# WiFi.net
KiCad netlist of a schematic drawn in Altium Designer
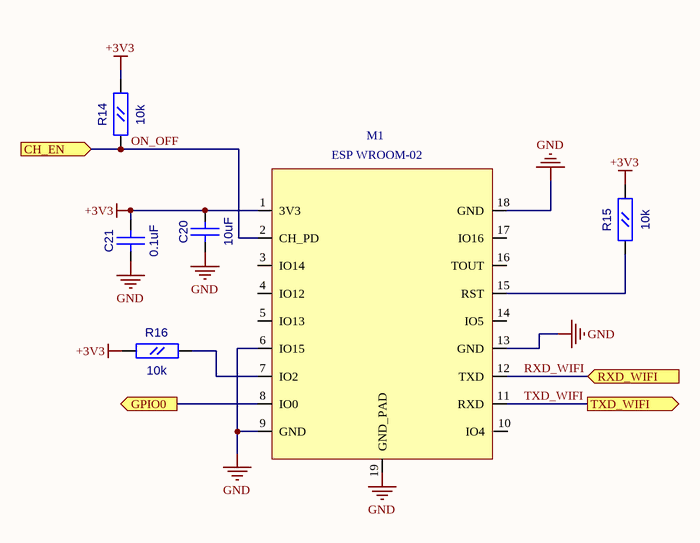
[diagram p0: WiFi.SchDoc]

(export (version "E")
  (design (tool "Eeschema 10.0.6"))
  (components
    (comp (ref "C20")
      (value "10uF")
      (footprint "CC0805")
      (description "CC0805")
      (libsource (lib "gprs_modem_2") (part "CC0805"))
    )
    (comp (ref "C21")
      (value "0.1uF")
      (footprint "CC0603")
      (description "CC0603")
      (libsource (lib "gprs_modem_2") (part "CC0603"))
    )
    (comp (ref "M1")
      (value "ESP WROOM-02")
      (footprint "ESP-WOORM-02")
      (libsource (lib "gprs_modem_2") (part "ESP-WROOM-02"))
    )
    (comp (ref "R14")
      (value "10k")
      (footprint "RC0603")
      (description "RC0603")
      (libsource (lib "gprs_modem_2") (part "RC0603"))
    )
    (comp (ref "R15")
      (value "10k")
      (footprint "RC0603")
      (description "RC0603")
      (libsource (lib "gprs_modem_2") (part "RC0603"))
    )
    (comp (ref "R16")
      (value "10k")
      (footprint "RC0603")
      (description "RC0603")
      (libsource (lib "gprs_modem_2") (part "RC0603"))
    )
  )
  (nets
    (net (code "1") (name "+3V3") (class "Default")
      (node (ref "C20") (pin "2") (pinfunction "B_2") (pintype "passive"))
      (node (ref "C21") (pin "2") (pinfunction "B_2") (pintype "passive"))
      (node (ref "M1") (pin "1") (pinfunction "3V3_1") (pintype "passive"))
      (node (ref "R14") (pin "2") (pinfunction "B_2") (pintype "passive"))
      (node (ref "R15") (pin "2") (pinfunction "B_2") (pintype "passive"))
      (node (ref "R16") (pin "1") (pinfunction "A_1") (pintype "passive"))
    )
    (net (code "2") (name "/GPIO0") (class "Default")
      (node (ref "M1") (pin "8") (pinfunction "IO0_8") (pintype "passive"))
    )
    (net (code "3") (name "/ON_OFF") (class "Default")
      (node (ref "M1") (pin "2") (pinfunction "CH_PD_2") (pintype "passive"))
      (node (ref "R14") (pin "1") (pinfunction "A_1") (pintype "passive"))
    )
    (net (code "4") (name "/RXD_WIFI") (class "Default")
      (node (ref "M1") (pin "12") (pinfunction "TXD_12") (pintype "passive"))
    )
    (net (code "5") (name "/TXD_WIFI") (class "Default")
      (node (ref "M1") (pin "11") (pinfunction "RXD_11") (pintype "passive"))
    )
    (net (code "6") (name "GND") (class "Default")
      (node (ref "C20") (pin "1") (pinfunction "A_1") (pintype "passive"))
      (node (ref "C21") (pin "1") (pinfunction "A_1") (pintype "passive"))
      (node (ref "M1") (pin "13") (pinfunction "GND_13") (pintype "passive"))
      (node (ref "M1") (pin "18") (pinfunction "GND_18") (pintype "passive"))
      (node (ref "M1") (pin "19") (pinfunction "GND_PAD_19") (pintype "passive"))
      (node (ref "M1") (pin "6") (pinfunction "IO15_6") (pintype "passive"))
      (node (ref "M1") (pin "9") (pinfunction "GND_9") (pintype "passive"))
    )
    (net (code "7") (name "Net-(M1-IO2)") (class "Default")
      (node (ref "M1") (pin "7") (pinfunction "IO2_7") (pintype "passive"))
      (node (ref "R16") (pin "2") (pinfunction "B_2") (pintype "passive"))
    )
    (net (code "8") (name "Net-(M1-RST)") (class "Default")
      (node (ref "M1") (pin "15") (pinfunction "RST_15") (pintype "passive"))
      (node (ref "R15") (pin "1") (pinfunction "A_1") (pintype "passive"))
    )
    (net (code "9") (name "unconnected-(M1-IO4-Pad10)") (class "Default")
      (node (ref "M1") (pin "10") (pinfunction "IO4_10") (pintype "passive"))
    )
    (net (code "10") (name "unconnected-(M1-IO5-Pad14)") (class "Default")
      (node (ref "M1") (pin "14") (pinfunction "IO5_14") (pintype "passive"))
    )
    (net (code "11") (name "unconnected-(M1-IO12-Pad4)") (class "Default")
      (node (ref "M1") (pin "4") (pinfunction "IO12_4") (pintype "passive"))
    )
    (net (code "12") (name "unconnected-(M1-IO13-Pad5)") (class "Default")
      (node (ref "M1") (pin "5") (pinfunction "IO13_5") (pintype "passive"))
    )
    (net (code "13") (name "unconnected-(M1-IO14-Pad3)") (class "Default")
      (node (ref "M1") (pin "3") (pinfunction "IO14_3") (pintype "passive"))
    )
    (net (code "14") (name "unconnected-(M1-IO16-Pad17)") (class "Default")
      (node (ref "M1") (pin "17") (pinfunction "IO16_17") (pintype "passive"))
    )
    (net (code "15") (name "unconnected-(M1-TOUT-Pad16)") (class "Default")
      (node (ref "M1") (pin "16") (pinfunction "TOUT_16") (pintype "passive"))
    )
  )
)
